# Power.net
KiCad netlist of a schematic drawn in Altium Designer
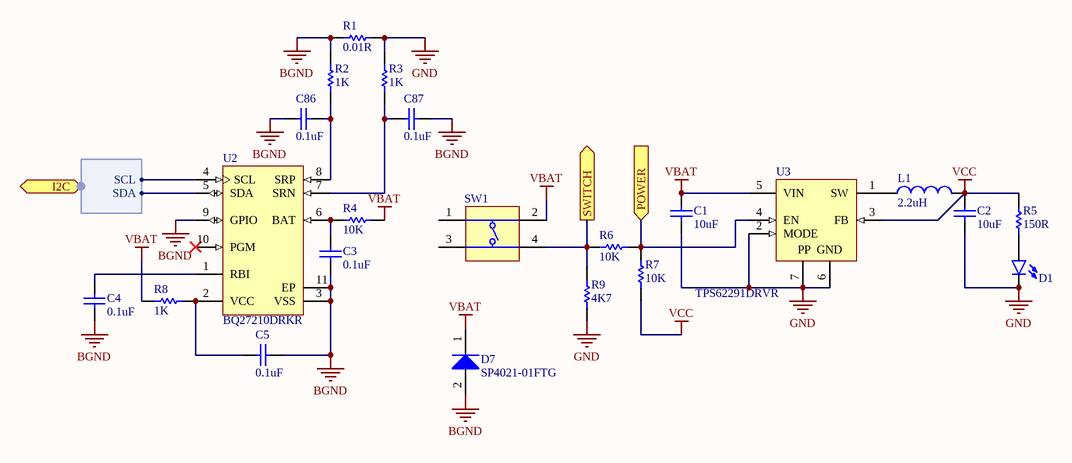
[diagram p0: Power.SchDoc]

(export (version "E")
  (design (tool "Eeschema 10.0.6"))
  (components
    (comp (ref "C1")
      (value "10uF")
      (footprint "C0402[1005X55]")
      (description "10uF 6.3V 20% 0402 (1005 Metric)")
      (fields (field (name "TOLERANCE") "20%") (field (name "PARTNUMBER") "GRM155R60J106ME44D"))
      (libsource (lib "Capacitors") (part "CAP_10uF_6.3V_0402_20%"))
    )
    (comp (ref "C2")
      (value "10uF")
      (footprint "C0402[1005X55]")
      (description "10uF 6.3V 20% 0402 (1005 Metric)")
      (fields (field (name "TOLERANCE") "20%") (field (name "PARTNUMBER") "GRM155R60J106ME44D"))
      (libsource (lib "Capacitors") (part "CAP_10uF_6.3V_0402_20%"))
    )
    (comp (ref "C3")
      (value "0.1uF")
      (footprint "C0402[1005X55]")
      (description "0.1uF 100V 10% 0402 (1005 Metric)")
      (fields (field (name "PARTNUMBER") "GRM155R62A104KE14D") (field (name "MANUFACTURER") "Murata"))
      (libsource (lib "Capacitors") (part "CAP_0.1uF_100V_0402_10%"))
    )
    (comp (ref "C4")
      (value "0.1uF")
      (footprint "C0402[1005X55]")
      (description "0.1uF 100V 10% 0402 (1005 Metric)")
      (fields (field (name "PARTNUMBER") "GRM155R62A104KE14D") (field (name "MANUFACTURER") "Murata"))
      (libsource (lib "Capacitors") (part "CAP_0.1uF_100V_0402_10%"))
    )
    (comp (ref "C5")
      (value "0.1uF")
      (footprint "C0402[1005X55]")
      (description "0.1uF 100V 10% 0402 (1005 Metric)")
      (fields (field (name "PARTNUMBER") "GRM155R62A104KE14D") (field (name "MANUFACTURER") "Murata"))
      (libsource (lib "Capacitors") (part "CAP_0.1uF_100V_0402_10%"))
    )
    (comp (ref "C86")
      (value "0.1uF")
      (footprint "C0402[1005X55]")
      (description "0.1uF 100V 10% 0402 (1005 Metric)")
      (fields (field (name "PARTNUMBER") "GRM155R62A104KE14D") (field (name "MANUFACTURER") "Murata"))
      (libsource (lib "Capacitors") (part "CAP_0.1uF_100V_0402_10%"))
    )
    (comp (ref "C87")
      (value "0.1uF")
      (footprint "C0402[1005X55]")
      (description "0.1uF 100V 10% 0402 (1005 Metric)")
      (fields (field (name "PARTNUMBER") "GRM155R62A104KE14D") (field (name "MANUFACTURER") "Murata"))
      (libsource (lib "Capacitors") (part "CAP_0.1uF_100V_0402_10%"))
    )
    (comp (ref "D1")
      (value "LED_0603_BLUE_5mA")
      (footprint "LED0603")
      (fields (field (name "PARTNUMBER") "LTST-C193TBKT-5A") (field (name "MANUFACTURER") "Lite-On Inc."))
      (libsource (lib "LEDs") (part "LED_0603_BLUE_5mA"))
    )
    (comp (ref "D7")
      (value "SP4021-01FTG")
      (footprint "SOD-323")
      (fields (field (name "MANUFACTURER") "Littelfuse"))
      (libsource (lib "Diodes") (part "SP4021-01FTG"))
    )
    (comp (ref "L1")
      (value "2.2uH")
      (footprint "IND0805")
      (description "2.2uH 20% 1.7A 0805")
      (fields (field (name "PARTNUMBER") "LQM21PN2R2MGHL") (field (name "MANUFACTURER") "Murata"))
      (libsource (lib "Inductors") (part "IND_2.2uH_1.7A_0805_20%"))
    )
    (comp (ref "R1")
      (value "0.01R")
      (footprint "R1206[3216]")
      (description "0.01R 1.5W 1% 1206 (3216 Metric)")
      (fields (field (name "MANUFACTURER") "KOA Speer") (field (name "PARTNUMBER") "TLR2BPDTD10L0F75"))
      (libsource (lib "Resistors") (part "RES_0.01R_1206_1%_1.5W"))
    )
    (comp (ref "R2")
      (value "1K")
      (footprint "R0402[1005]")
      (description "1K 0.063W 1% 0402 (1005 Metric)")
      (fields (field (name "MANUFACTURER") "KOA Speer") (field (name "PARTNUMBER") "RK73H1ETTP1001F"))
      (libsource (lib "Resistors") (part "RES_1K_0402_1%"))
    )
    (comp (ref "R3")
      (value "1K")
      (footprint "R0402[1005]")
      (description "1K 0.063W 1% 0402 (1005 Metric)")
      (fields (field (name "MANUFACTURER") "KOA Speer") (field (name "PARTNUMBER") "RK73H1ETTP1001F"))
      (libsource (lib "Resistors") (part "RES_1K_0402_1%"))
    )
    (comp (ref "R4")
      (value "10K")
      (footprint "R0402[1005]")
      (description "10K 0.063W 1% 0402 (1005 Metric)")
      (fields (field (name "MANUFACTURER") "KOA Speer") (field (name "PARTNUMBER") "RK73H1ETTP1002F"))
      (libsource (lib "Resistors") (part "RES_10K_0402_1%"))
    )
    (comp (ref "R5")
      (value "150R")
      (footprint "R0402[1005]")
      (description "150R 0.063W 1% 0402 (1005 Metric)")
      (fields (field (name "MANUFACTURER") "KOA Speer") (field (name "PARTNUMBER") "RK73H1ETTP1500F"))
      (libsource (lib "Resistors") (part "RES_150R_0402_1%"))
    )
    (comp (ref "R6")
      (value "10K")
      (footprint "R0402[1005]")
      (description "10K 0.063W 1% 0402 (1005 Metric)")
      (fields (field (name "MANUFACTURER") "KOA Speer") (field (name "PARTNUMBER") "RK73H1ETTP1002F"))
      (libsource (lib "Resistors") (part "RES_10K_0402_1%"))
    )
    (comp (ref "R7")
      (value "10K")
      (footprint "R0402[1005]")
      (description "10K 0.063W 1% 0402 (1005 Metric)")
      (fields (field (name "MANUFACTURER") "KOA Speer") (field (name "PARTNUMBER") "RK73H1ETTP1002F"))
      (libsource (lib "Resistors") (part "RES_10K_0402_1%"))
    )
    (comp (ref "R8")
      (value "1K")
      (footprint "R0402[1005]")
      (description "1K 0.063W 1% 0402 (1005 Metric)")
      (fields (field (name "MANUFACTURER") "KOA Speer") (field (name "PARTNUMBER") "RK73H1ETTP1001F"))
      (libsource (lib "Resistors") (part "RES_1K_0402_1%"))
    )
    (comp (ref "R9")
      (value "4K7")
      (footprint "R0402[1005]")
      (description "4K7 0.063W 1% 0402 (1005 Metric)")
      (fields (field (name "MANUFACTURER") "KOA Speer") (field (name "PARTNUMBER") "RK73H1ETTP4701F"))
      (libsource (lib "Resistors") (part "RES_4K7_0402_1%"))
    )
    (comp (ref "SW1")
      (value "~")
      (footprint "SWITCH")
      (description "Switch, SPNO Push Button SMD")
      (fields
        (field (name "MANUFACTURER") "C&K Components")
        (field (name "PARTNUMBER") "PTS810 SJM 250 SMTR LFS")
      )
      (libsource (lib "Components") (part "DIPT-DTSM-6"))
    )
    (comp (ref "U2")
      (value "BQ27210DRKR")
      (footprint "VSON-10")
      (fields (field (name "MANUFACTURER") "Texas Instruments"))
      (libsource (lib "ICs") (part "BQ27210DRKR"))
    )
    (comp (ref "U3")
      (value "TPS62291DRVR")
      (footprint "WSON-6")
      (description "Voltage Regulators - Switching Regulators 2.25MHz 1A Step-Down Cnvrtr 3.3V Output")
      (fields (field (name "MANUFACTURER") "Texas Instruments"))
      (libsource (lib "ICs") (part "TPS62291DRVR"))
    )
  )
  (nets
    (net (code "2") (name "/POWER") (class "Default")
      (node (ref "R6") (pin "2") (pinfunction "2_2") (pintype "passive"))
      (node (ref "R7") (pin "2") (pinfunction "2_2") (pintype "passive"))
      (node (ref "U3") (pin "4") (pinfunction "EN_4") (pintype "input"))
    )
    (net (code "3") (name "/SCL") (class "Default")
      (node (ref "U2") (pin "4") (pinfunction "SCL_4") (pintype "input"))
    )
    (net (code "4") (name "/SDA") (class "Default")
      (node (ref "U2") (pin "5") (pinfunction "SDA_5") (pintype "bidirectional"))
    )
    (net (code "5") (name "/SWITCH") (class "Default")
      (node (ref "R6") (pin "1") (pinfunction "1_1") (pintype "passive"))
      (node (ref "R9") (pin "2") (pinfunction "2_2") (pintype "passive"))
      (node (ref "SW1") (pin "4") (pinfunction "T3_4") (pintype "passive"))
    )
    (net (code "7") (name "BGND") (class "Default")
      (node (ref "C3") (pin "1") (pinfunction "1_1") (pintype "passive"))
      (node (ref "C4") (pin "1") (pinfunction "1_1") (pintype "passive"))
      (node (ref "C5") (pin "2") (pinfunction "2_2") (pintype "passive"))
      (node (ref "C86") (pin "1") (pinfunction "1_1") (pintype "passive"))
      (node (ref "C87") (pin "2") (pinfunction "2_2") (pintype "passive"))
      (node (ref "D7") (pin "2") (pinfunction "A_2") (pintype "passive"))
      (node (ref "R1") (pin "1") (pinfunction "1_1") (pintype "passive"))
      (node (ref "R2") (pin "2") (pinfunction "2_2") (pintype "passive"))
      (node (ref "U2") (pin "11") (pinfunction "EP_11") (pintype "power_in"))
      (node (ref "U2") (pin "3") (pinfunction "VSS_3") (pintype "power_in"))
      (node (ref "U2") (pin "9") (pinfunction "GPIO_9") (pintype "bidirectional"))
    )
    (net (code "8") (name "GND") (class "Default")
      (node (ref "C1") (pin "1") (pinfunction "1_1") (pintype "passive"))
      (node (ref "C2") (pin "1") (pinfunction "1_1") (pintype "passive"))
      (node (ref "D1") (pin "C") (pinfunction "C_C") (pintype "passive"))
      (node (ref "R1") (pin "2") (pinfunction "2_2") (pintype "passive"))
      (node (ref "R3") (pin "2") (pinfunction "2_2") (pintype "passive"))
      (node (ref "R9") (pin "1") (pinfunction "1_1") (pintype "passive"))
      (node (ref "U3") (pin "2") (pinfunction "MODE_2") (pintype "input"))
      (node (ref "U3") (pin "6") (pinfunction "GND_6") (pintype "power_in"))
      (node (ref "U3") (pin "7") (pinfunction "EP_7") (pintype "passive"))
    )
    (net (code "9") (name "Net-(D1-PadA)") (class "Default")
      (node (ref "D1") (pin "A") (pinfunction "A_A") (pintype "passive"))
      (node (ref "R5") (pin "2") (pinfunction "2_2") (pintype "passive"))
    )
    (net (code "10") (name "Net-(U2-BAT)") (class "Default")
      (node (ref "C3") (pin "2") (pinfunction "2_2") (pintype "passive"))
      (node (ref "R4") (pin "1") (pinfunction "1_1") (pintype "passive"))
      (node (ref "U2") (pin "6") (pinfunction "BAT_6") (pintype "input"))
    )
    (net (code "11") (name "Net-(U2-RBI)") (class "Default")
      (node (ref "C4") (pin "2") (pinfunction "2_2") (pintype "passive"))
      (node (ref "U2") (pin "1") (pinfunction "RBI_1") (pintype "power_in"))
    )
    (net (code "12") (name "Net-(U2-SRN)") (class "Default")
      (node (ref "C87") (pin "1") (pinfunction "1_1") (pintype "passive"))
      (node (ref "R3") (pin "1") (pinfunction "1_1") (pintype "passive"))
      (node (ref "U2") (pin "7") (pinfunction "SRN_7") (pintype "input"))
    )
    (net (code "13") (name "Net-(U2-SRP)") (class "Default")
      (node (ref "C86") (pin "2") (pinfunction "2_2") (pintype "passive"))
      (node (ref "R2") (pin "1") (pinfunction "1_1") (pintype "passive"))
      (node (ref "U2") (pin "8") (pinfunction "SRP_8") (pintype "input"))
    )
    (net (code "14") (name "Net-(U2-VCC)") (class "Default")
      (node (ref "C5") (pin "1") (pinfunction "1_1") (pintype "passive"))
      (node (ref "R8") (pin "1") (pinfunction "1_1") (pintype "passive"))
      (node (ref "U2") (pin "2") (pinfunction "VCC_2") (pintype "power_in"))
    )
    (net (code "15") (name "Net-(U3-SW)") (class "Default")
      (node (ref "L1") (pin "1") (pinfunction "1_1") (pintype "passive"))
      (node (ref "U3") (pin "1") (pinfunction "SW_1") (pintype "power_in"))
    )
    (net (code "16") (name "VBAT") (class "Default")
      (node (ref "C1") (pin "2") (pinfunction "2_2") (pintype "passive"))
      (node (ref "D7") (pin "1") (pinfunction "K_1") (pintype "passive"))
      (node (ref "R4") (pin "2") (pinfunction "2_2") (pintype "passive"))
      (node (ref "R8") (pin "2") (pinfunction "2_2") (pintype "passive"))
      (node (ref "SW1") (pin "2") (pinfunction "T2_2") (pintype "passive"))
      (node (ref "U3") (pin "5") (pinfunction "VIN_5") (pintype "power_in"))
    )
    (net (code "17") (name "VCC") (class "Default")
      (node (ref "C2") (pin "2") (pinfunction "2_2") (pintype "passive"))
      (node (ref "L1") (pin "2") (pinfunction "2_2") (pintype "passive"))
      (node (ref "R5") (pin "1") (pinfunction "1_1") (pintype "passive"))
      (node (ref "R7") (pin "1") (pinfunction "1_1") (pintype "passive"))
      (node (ref "U3") (pin "3") (pinfunction "FB_3") (pintype "input"))
    )
    (net (code "18") (name "unconnected-(SW1-T1-Pad1)") (class "Default")
      (node (ref "SW1") (pin "1") (pinfunction "T1_1") (pintype "passive"))
    )
    (net (code "19") (name "unconnected-(SW1-T3-Pad3)") (class "Default")
      (node (ref "SW1") (pin "3") (pinfunction "T3_3") (pintype "passive"))
    )
    (net (code "20") (name "unconnected-(U2-PGM-Pad10)") (class "Default")
      (node (ref "U2") (pin "10") (pinfunction "PGM_10") (pintype "input+no_connect"))
    )
  )
)
